# IR_module_V3.net
KiCad netlist of a schematic drawn in EAGLE
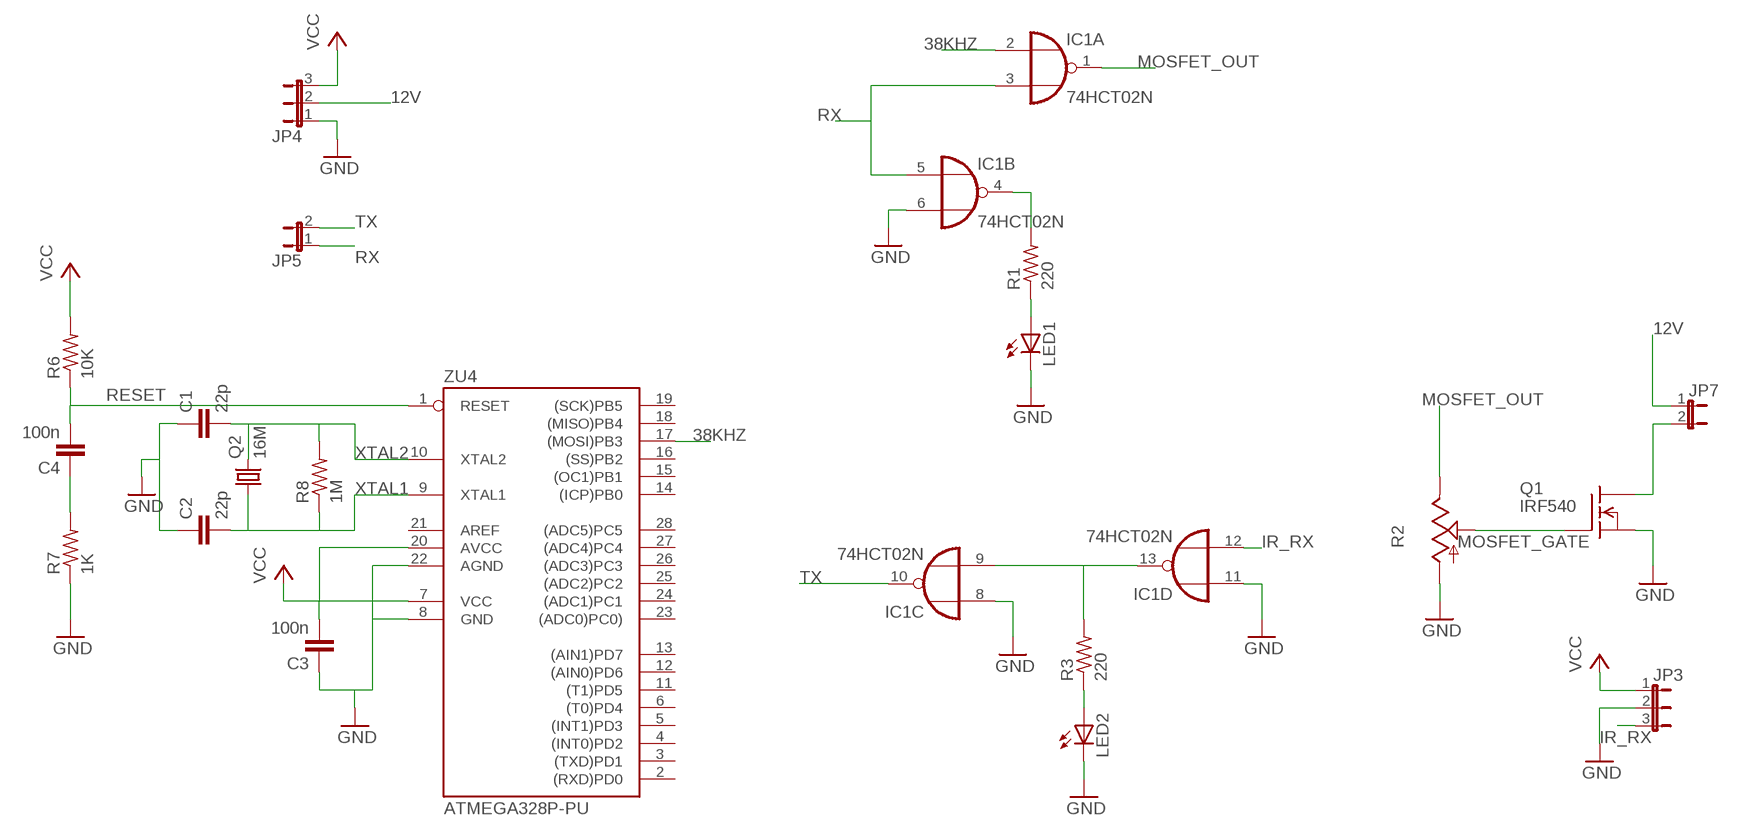
[diagram p0: schematic, sheet 1]

(export (version "E")
  (design (tool "Eeschema 10.0.6"))
  (components
    (comp (ref "C1")
      (value "22p")
      (footprint "eagle-import:CAP-PTH-SMALLEZ")
      (libsource (lib "eagle-import") (part "CAPEZ"))
    )
    (comp (ref "C2")
      (value "22p")
      (footprint "eagle-import:CAP-PTH-SMALLEZ")
      (libsource (lib "eagle-import") (part "CAPEZ"))
    )
    (comp (ref "C3")
      (value "100n")
      (footprint "eagle-import:CAP-PTH-SMALLEZ")
      (libsource (lib "eagle-import") (part "CAPEZ"))
    )
    (comp (ref "C4")
      (value "100n")
      (footprint "eagle-import:CAP-PTH-SMALLEZ")
      (libsource (lib "eagle-import") (part "CAPEZ"))
    )
    (comp (ref "IC1")
      (value "74HCT02N")
      (footprint "eagle-import:DIL14")
      (libsource (lib "eagle-import") (part "7402NHCT"))
    )
    (comp (ref "JP3")
      (value "JP2E")
      (footprint "eagle-import:JP2")
      (libsource (lib "eagle-import") (part "JP2E"))
    )
    (comp (ref "JP4")
      (value "JP2E")
      (footprint "eagle-import:JP2")
      (libsource (lib "eagle-import") (part "JP2E"))
    )
    (comp (ref "JP5")
      (value "JP1E")
      (footprint "eagle-import:JP1")
      (libsource (lib "eagle-import") (part "JP1E"))
    )
    (comp (ref "JP7")
      (value "JP1E")
      (footprint "eagle-import:JP1")
      (libsource (lib "eagle-import") (part "JP1E"))
    )
    (comp (ref "LED1")
      (value "LED5MM")
      (footprint "eagle-import:LED5MM")
      (libsource (lib "eagle-import") (part "LED5MM"))
    )
    (comp (ref "LED2")
      (value "LED5MM")
      (footprint "eagle-import:LED5MM")
      (libsource (lib "eagle-import") (part "LED5MM"))
    )
    (comp (ref "Q1")
      (value "IRF540")
      (footprint "eagle-import:TO220")
      (libsource (lib "eagle-import") (part "IRF540"))
    )
    (comp (ref "Q2")
      (value "16M")
      (footprint "eagle-import:HC49_S")
      (libsource (lib "eagle-import") (part "CRYSTALHC49S"))
    )
    (comp (ref "R1")
      (value "220")
      (footprint "eagle-import:0207_10")
      (libsource (lib "eagle-import") (part "R-US_0207/10"))
    )
    (comp (ref "R2")
      (value "TRIM_US-B25P")
      (footprint "eagle-import:B25P")
      (libsource (lib "eagle-import") (part "TRIM_US-B25P"))
    )
    (comp (ref "R3")
      (value "220")
      (footprint "eagle-import:0207_10")
      (libsource (lib "eagle-import") (part "R-US_0207/10"))
    )
    (comp (ref "R6")
      (value "10K")
      (footprint "eagle-import:0207_10")
      (libsource (lib "eagle-import") (part "R-US_0207/10"))
    )
    (comp (ref "R7")
      (value "1K")
      (footprint "eagle-import:0207_10")
      (libsource (lib "eagle-import") (part "R-US_0207/10"))
    )
    (comp (ref "R8")
      (value "1M")
      (footprint "eagle-import:0207_10")
      (libsource (lib "eagle-import") (part "R-US_0207/10"))
    )
    (comp (ref "ZU4")
      (value "ATMEGA328P-PU")
      (footprint "eagle-import:DIL28-3")
      (libsource (lib "eagle-import") (part "ATMEGA328P-PU"))
    )
  )
  (nets
    (net (code "1") (name "/12V") (class "Default")
      (node (ref "JP4") (pin "2") (pinfunction "2_2") (pintype "passive"))
      (node (ref "JP7") (pin "1") (pinfunction "1_1") (pintype "passive"))
    )
    (net (code "2") (name "/38KHZ") (class "Default")
      (node (ref "IC1") (pin "2") (pinfunction "I0_2") (pintype "input"))
      (node (ref "ZU4") (pin "17") (pinfunction "(MOSI)PB3_17") (pintype "bidirectional"))
    )
    (net (code "3") (name "/IR_RX") (class "Default")
      (node (ref "IC1") (pin "12") (pinfunction "I1_12") (pintype "input"))
      (node (ref "JP3") (pin "3") (pinfunction "3_3") (pintype "passive"))
    )
    (net (code "4") (name "/MOSFET_GATE") (class "Default")
      (node (ref "Q1") (pin "1") (pinfunction "G_1") (pintype "passive"))
      (node (ref "R2") (pin "S") (pinfunction "S_S") (pintype "passive"))
    )
    (net (code "5") (name "/MOSFET_OUT") (class "Default")
      (node (ref "IC1") (pin "1") (pinfunction "O_1") (pintype "output"))
      (node (ref "R2") (pin "E") (pinfunction "E_E") (pintype "passive"))
    )
    (net (code "6") (name "/RESET") (class "Default")
      (node (ref "C4") (pin "2") (pinfunction "2_2") (pintype "passive"))
      (node (ref "R6") (pin "1") (pinfunction "1_1") (pintype "passive"))
      (node (ref "ZU4") (pin "1") (pinfunction "RESET_1") (pintype "input"))
    )
    (net (code "7") (name "/RX") (class "Default")
      (node (ref "IC1") (pin "3") (pinfunction "I1_3") (pintype "input"))
      (node (ref "IC1") (pin "5") (pinfunction "I0_5") (pintype "input"))
      (node (ref "JP5") (pin "1") (pinfunction "1_1") (pintype "passive"))
    )
    (net (code "8") (name "/TX") (class "Default")
      (node (ref "IC1") (pin "10") (pinfunction "O_10") (pintype "output"))
      (node (ref "JP5") (pin "2") (pinfunction "2_2") (pintype "passive"))
    )
    (net (code "9") (name "/XTAL1") (class "Default")
      (node (ref "C2") (pin "2") (pinfunction "2_2") (pintype "passive"))
      (node (ref "Q2") (pin "1") (pinfunction "1_1") (pintype "passive"))
      (node (ref "R8") (pin "1") (pinfunction "1_1") (pintype "passive"))
      (node (ref "ZU4") (pin "9") (pinfunction "XTAL1_9") (pintype "bidirectional"))
    )
    (net (code "10") (name "/XTAL2") (class "Default")
      (node (ref "C1") (pin "2") (pinfunction "2_2") (pintype "passive"))
      (node (ref "Q2") (pin "2") (pinfunction "2_2") (pintype "passive"))
      (node (ref "R8") (pin "2") (pinfunction "2_2") (pintype "passive"))
      (node (ref "ZU4") (pin "10") (pinfunction "XTAL2_10") (pintype "bidirectional"))
    )
    (net (code "11") (name "GND") (class "Default")
      (node (ref "C1") (pin "1") (pinfunction "1_1") (pintype "passive"))
      (node (ref "C2") (pin "1") (pinfunction "1_1") (pintype "passive"))
      (node (ref "C3") (pin "1") (pinfunction "1_1") (pintype "passive"))
      (node (ref "IC1") (pin "11") (pinfunction "I0_11") (pintype "input"))
      (node (ref "IC1") (pin "6") (pinfunction "I1_6") (pintype "input"))
      (node (ref "IC1") (pin "8") (pinfunction "I0_8") (pintype "input"))
      (node (ref "JP3") (pin "2") (pinfunction "2_2") (pintype "passive"))
      (node (ref "JP4") (pin "1") (pinfunction "1_1") (pintype "passive"))
      (node (ref "LED1") (pin "K") (pinfunction "C_K") (pintype "passive"))
      (node (ref "LED2") (pin "K") (pinfunction "C_K") (pintype "passive"))
      (node (ref "Q1") (pin "3") (pinfunction "S_3") (pintype "passive"))
      (node (ref "R2") (pin "A") (pinfunction "A_A") (pintype "passive"))
      (node (ref "R7") (pin "1") (pinfunction "1_1") (pintype "passive"))
      (node (ref "ZU4") (pin "22") (pinfunction "AGND_22") (pintype "power_in"))
      (node (ref "ZU4") (pin "8") (pinfunction "GND_8") (pintype "power_in"))
    )
    (net (code "12") (name "Net-(C4-Pad1)") (class "Default")
      (node (ref "C4") (pin "1") (pinfunction "1_1") (pintype "passive"))
      (node (ref "R7") (pin "2") (pinfunction "2_2") (pintype "passive"))
    )
    (net (code "13") (name "Net-(IC1B-O)") (class "Default")
      (node (ref "IC1") (pin "4") (pinfunction "O_4") (pintype "output"))
      (node (ref "R1") (pin "2") (pinfunction "2_2") (pintype "passive"))
    )
    (net (code "14") (name "Net-(IC1C-I1)") (class "Default")
      (node (ref "IC1") (pin "13") (pinfunction "O_13") (pintype "output"))
      (node (ref "IC1") (pin "9") (pinfunction "I1_9") (pintype "input"))
      (node (ref "R3") (pin "2") (pinfunction "2_2") (pintype "passive"))
    )
    (net (code "15") (name "Net-(LED1-PadA)") (class "Default")
      (node (ref "LED1") (pin "A") (pinfunction "A_A") (pintype "passive"))
      (node (ref "R1") (pin "1") (pinfunction "1_1") (pintype "passive"))
    )
    (net (code "16") (name "Net-(LED2-PadA)") (class "Default")
      (node (ref "LED2") (pin "A") (pinfunction "A_A") (pintype "passive"))
      (node (ref "R3") (pin "1") (pinfunction "1_1") (pintype "passive"))
    )
    (net (code "17") (name "Net-(Q1-D)") (class "Default")
      (node (ref "JP7") (pin "2") (pinfunction "2_2") (pintype "passive"))
      (node (ref "Q1") (pin "2") (pinfunction "D_2") (pintype "passive"))
    )
    (net (code "18") (name "VCC") (class "Default")
      (node (ref "C3") (pin "2") (pinfunction "2_2") (pintype "passive"))
      (node (ref "JP3") (pin "1") (pinfunction "1_1") (pintype "passive"))
      (node (ref "JP4") (pin "3") (pinfunction "3_3") (pintype "passive"))
      (node (ref "R6") (pin "2") (pinfunction "2_2") (pintype "passive"))
      (node (ref "ZU4") (pin "20") (pinfunction "AVCC_20") (pintype "power_in"))
      (node (ref "ZU4") (pin "7") (pinfunction "VCC_7") (pintype "power_in"))
    )
    (net (code "19") (name "unconnected-(ZU4-(ADC0)PC0)-Pad23)") (class "Default")
      (node (ref "ZU4") (pin "23") (pinfunction "(ADC0)PC0)_23") (pintype "bidirectional"))
    )
    (net (code "20") (name "unconnected-(ZU4-(ADC1)PC1-Pad24)") (class "Default")
      (node (ref "ZU4") (pin "24") (pinfunction "(ADC1)PC1_24") (pintype "bidirectional"))
    )
    (net (code "21") (name "unconnected-(ZU4-(ADC2)PC2-Pad25)") (class "Default")
      (node (ref "ZU4") (pin "25") (pinfunction "(ADC2)PC2_25") (pintype "bidirectional"))
    )
    (net (code "22") (name "unconnected-(ZU4-(ADC3)PC3-Pad26)") (class "Default")
      (node (ref "ZU4") (pin "26") (pinfunction "(ADC3)PC3_26") (pintype "bidirectional"))
    )
    (net (code "23") (name "unconnected-(ZU4-(ADC4)PC4-Pad27)") (class "Default")
      (node (ref "ZU4") (pin "27") (pinfunction "(ADC4)PC4_27") (pintype "bidirectional"))
    )
    (net (code "24") (name "unconnected-(ZU4-(ADC5)PC5-Pad28)") (class "Default")
      (node (ref "ZU4") (pin "28") (pinfunction "(ADC5)PC5_28") (pintype "bidirectional"))
    )
    (net (code "25") (name "unconnected-(ZU4-(AIN0)PD6-Pad12)") (class "Default")
      (node (ref "ZU4") (pin "12") (pinfunction "(AIN0)PD6_12") (pintype "bidirectional"))
    )
    (net (code "26") (name "unconnected-(ZU4-(AIN1)PD7-Pad13)") (class "Default")
      (node (ref "ZU4") (pin "13") (pinfunction "(AIN1)PD7_13") (pintype "bidirectional"))
    )
    (net (code "27") (name "unconnected-(ZU4-(ICP)PB0-Pad14)") (class "Default")
      (node (ref "ZU4") (pin "14") (pinfunction "(ICP)PB0_14") (pintype "bidirectional"))
    )
    (net (code "28") (name "unconnected-(ZU4-(INT0)PD2-Pad4)") (class "Default")
      (node (ref "ZU4") (pin "4") (pinfunction "(INT0)PD2_4") (pintype "bidirectional"))
    )
    (net (code "29") (name "unconnected-(ZU4-(INT1)PD3-Pad5)") (class "Default")
      (node (ref "ZU4") (pin "5") (pinfunction "(INT1)PD3_5") (pintype "bidirectional"))
    )
    (net (code "30") (name "unconnected-(ZU4-(MISO)PB4-Pad18)") (class "Default")
      (node (ref "ZU4") (pin "18") (pinfunction "(MISO)PB4_18") (pintype "bidirectional"))
    )
    (net (code "31") (name "unconnected-(ZU4-(OC1)PB1-Pad15)") (class "Default")
      (node (ref "ZU4") (pin "15") (pinfunction "(OC1)PB1_15") (pintype "bidirectional"))
    )
    (net (code "32") (name "unconnected-(ZU4-(RXD)PD0-Pad2)") (class "Default")
      (node (ref "ZU4") (pin "2") (pinfunction "(RXD)PD0_2") (pintype "bidirectional"))
    )
    (net (code "33") (name "unconnected-(ZU4-(SCK)PB5-Pad19)") (class "Default")
      (node (ref "ZU4") (pin "19") (pinfunction "(SCK)PB5_19") (pintype "bidirectional"))
    )
    (net (code "34") (name "unconnected-(ZU4-(SS)PB2-Pad16)") (class "Default")
      (node (ref "ZU4") (pin "16") (pinfunction "(SS)PB2_16") (pintype "bidirectional"))
    )
    (net (code "35") (name "unconnected-(ZU4-(T0)PD4-Pad6)") (class "Default")
      (node (ref "ZU4") (pin "6") (pinfunction "(T0)PD4_6") (pintype "bidirectional"))
    )
    (net (code "36") (name "unconnected-(ZU4-(T1)PD5-Pad11)") (class "Default")
      (node (ref "ZU4") (pin "11") (pinfunction "(T1)PD5_11") (pintype "bidirectional"))
    )
    (net (code "37") (name "unconnected-(ZU4-(TXD)PD1-Pad3)") (class "Default")
      (node (ref "ZU4") (pin "3") (pinfunction "(TXD)PD1_3") (pintype "bidirectional"))
    )
    (net (code "38") (name "unconnected-(ZU4-AREF-Pad21)") (class "Default")
      (node (ref "ZU4") (pin "21") (pinfunction "AREF_21") (pintype "passive"))
    )
  )
)
